# LED_BLOCK.net
KiCad netlist of a schematic drawn in Altium Designer
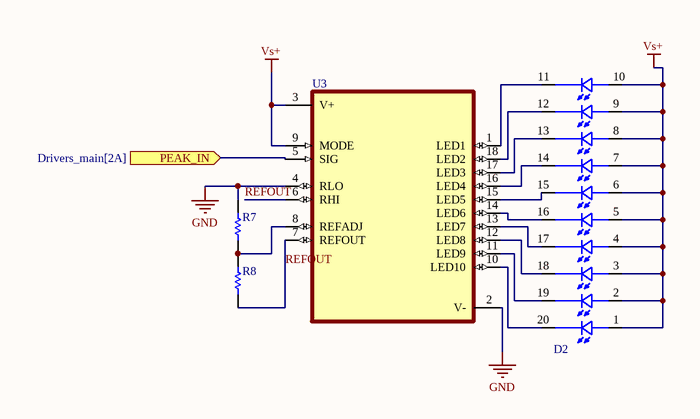
[diagram p0: LED_BLOCK.SchDoc]

(export (version "E")
  (design (tool "Eeschema 10.0.6"))
  (components
    (comp (ref "D2")
      (value "DC10EWA")
      (footprint "DIP750W50P254L2540H825Q20")
      (description "LED Circuit Board Indicator Bar - 10 Wide, DIP Red (x 10) Diffused, White 2V 30mA Through Hole")
      (fields (field (name "MF") "Kingbright"))
      (libsource (lib "Schlib1") (part "DC10EWA"))
    )
    (comp (ref "R7")
      (value "MFR-25FBF5210K")
      (footprint "RESA60-630X240")
      (description "Axial Resistor, 10 KOhm, +/- 1%, 0.25 W, -55 to 155 degC, 2-Pin THD, RoHS, Bulk")
      (fields (field (name "TOLERANCE") "1%") (field (name "MANUFACTURER") "Yageo"))
      (libsource (lib "Altium Content Vault") (part "RES-2"))
    )
    (comp (ref "R8")
      (value "MFR-25FBF5210K")
      (footprint "RESA60-630X240")
      (description "Axial Resistor, 10 KOhm, +/- 1%, 0.25 W, -55 to 155 degC, 2-Pin THD, RoHS, Bulk")
      (fields (field (name "TOLERANCE") "1%") (field (name "MANUFACTURER") "Yageo"))
      (libsource (lib "Altium Content Vault") (part "RES-2"))
    )
    (comp (ref "U3")
      (value "LM3914N-1")
      (footprint "DIP952W45P254L2336H533Q18")
      (description "LED, LCD, Vacuum Fluorescent (VF) Driver 18-PDIP")
      (fields (field (name "MF") "Texas Instruments"))
      (libsource (lib "Schlib1") (part "LM3914N-1"))
    )
  )
  (nets
    (net (code "1") (name "/PEAK_IN") (class "Default")
      (node (ref "U3") (pin "5") (pinfunction "SIG_5") (pintype "input"))
    )
    (net (code "2") (name "/REFOUT") (class "Default")
      (node (ref "R8") (pin "1") (pinfunction "1_1") (pintype "passive"))
      (node (ref "U3") (pin "6") (pinfunction "RHI_6") (pintype "bidirectional"))
      (node (ref "U3") (pin "7") (pinfunction "REFOUT_7") (pintype "bidirectional"))
    )
    (net (code "3") (name "GND") (class "Default")
      (node (ref "R7") (pin "2") (pinfunction "2_2") (pintype "passive"))
      (node (ref "U3") (pin "2") (pinfunction "V-_2") (pintype "power_in"))
      (node (ref "U3") (pin "4") (pinfunction "RLO_4") (pintype "bidirectional"))
    )
    (net (code "4") (name "Net-(U3-LED1)") (class "Default")
      (node (ref "D2") (pin "11") (pinfunction "11_11") (pintype "passive"))
      (node (ref "U3") (pin "1") (pinfunction "LED1_1") (pintype "bidirectional"))
    )
    (net (code "5") (name "Net-(U3-LED2)") (class "Default")
      (node (ref "D2") (pin "12") (pinfunction "12_12") (pintype "passive"))
      (node (ref "U3") (pin "18") (pinfunction "LED2_18") (pintype "bidirectional"))
    )
    (net (code "6") (name "Net-(U3-LED3)") (class "Default")
      (node (ref "D2") (pin "13") (pinfunction "13_13") (pintype "passive"))
      (node (ref "U3") (pin "17") (pinfunction "LED3_17") (pintype "bidirectional"))
    )
    (net (code "7") (name "Net-(U3-LED4)") (class "Default")
      (node (ref "D2") (pin "14") (pinfunction "14_14") (pintype "passive"))
      (node (ref "U3") (pin "16") (pinfunction "LED4_16") (pintype "bidirectional"))
    )
    (net (code "8") (name "Net-(U3-LED5)") (class "Default")
      (node (ref "D2") (pin "15") (pinfunction "15_15") (pintype "passive"))
      (node (ref "U3") (pin "15") (pinfunction "LED5_15") (pintype "bidirectional"))
    )
    (net (code "9") (name "Net-(U3-LED6)") (class "Default")
      (node (ref "D2") (pin "16") (pinfunction "16_16") (pintype "passive"))
      (node (ref "U3") (pin "14") (pinfunction "LED6_14") (pintype "bidirectional"))
    )
    (net (code "10") (name "Net-(U3-LED7)") (class "Default")
      (node (ref "D2") (pin "17") (pinfunction "17_17") (pintype "passive"))
      (node (ref "U3") (pin "13") (pinfunction "LED7_13") (pintype "bidirectional"))
    )
    (net (code "11") (name "Net-(U3-LED8)") (class "Default")
      (node (ref "D2") (pin "18") (pinfunction "18_18") (pintype "passive"))
      (node (ref "U3") (pin "12") (pinfunction "LED8_12") (pintype "bidirectional"))
    )
    (net (code "12") (name "Net-(U3-LED9)") (class "Default")
      (node (ref "D2") (pin "19") (pinfunction "19_19") (pintype "passive"))
      (node (ref "U3") (pin "11") (pinfunction "LED9_11") (pintype "bidirectional"))
    )
    (net (code "13") (name "Net-(U3-LED10)") (class "Default")
      (node (ref "D2") (pin "20") (pinfunction "20_20") (pintype "passive"))
      (node (ref "U3") (pin "10") (pinfunction "LED10_10") (pintype "bidirectional"))
    )
    (net (code "14") (name "Net-(U3-REFADJ)") (class "Default")
      (node (ref "R7") (pin "1") (pinfunction "1_1") (pintype "passive"))
      (node (ref "R8") (pin "2") (pinfunction "2_2") (pintype "passive"))
      (node (ref "U3") (pin "8") (pinfunction "REFADJ_8") (pintype "bidirectional"))
    )
    (net (code "15") (name "Vs+") (class "Default")
      (node (ref "D2") (pin "1") (pinfunction "1_1") (pintype "passive"))
      (node (ref "D2") (pin "10") (pinfunction "10_10") (pintype "passive"))
      (node (ref "D2") (pin "2") (pinfunction "2_2") (pintype "passive"))
      (node (ref "D2") (pin "3") (pinfunction "3_3") (pintype "passive"))
      (node (ref "D2") (pin "4") (pinfunction "4_4") (pintype "passive"))
      (node (ref "D2") (pin "5") (pinfunction "5_5") (pintype "passive"))
      (node (ref "D2") (pin "6") (pinfunction "6_6") (pintype "passive"))
      (node (ref "D2") (pin "7") (pinfunction "7_7") (pintype "passive"))
      (node (ref "D2") (pin "8") (pinfunction "8_8") (pintype "passive"))
      (node (ref "D2") (pin "9") (pinfunction "9_9") (pintype "passive"))
      (node (ref "U3") (pin "3") (pinfunction "V+_3") (pintype "power_in"))
      (node (ref "U3") (pin "9") (pinfunction "MODE_9") (pintype "input"))
    )
  )
)
